# Services.net
KiCad netlist of a schematic drawn in Altium Designer
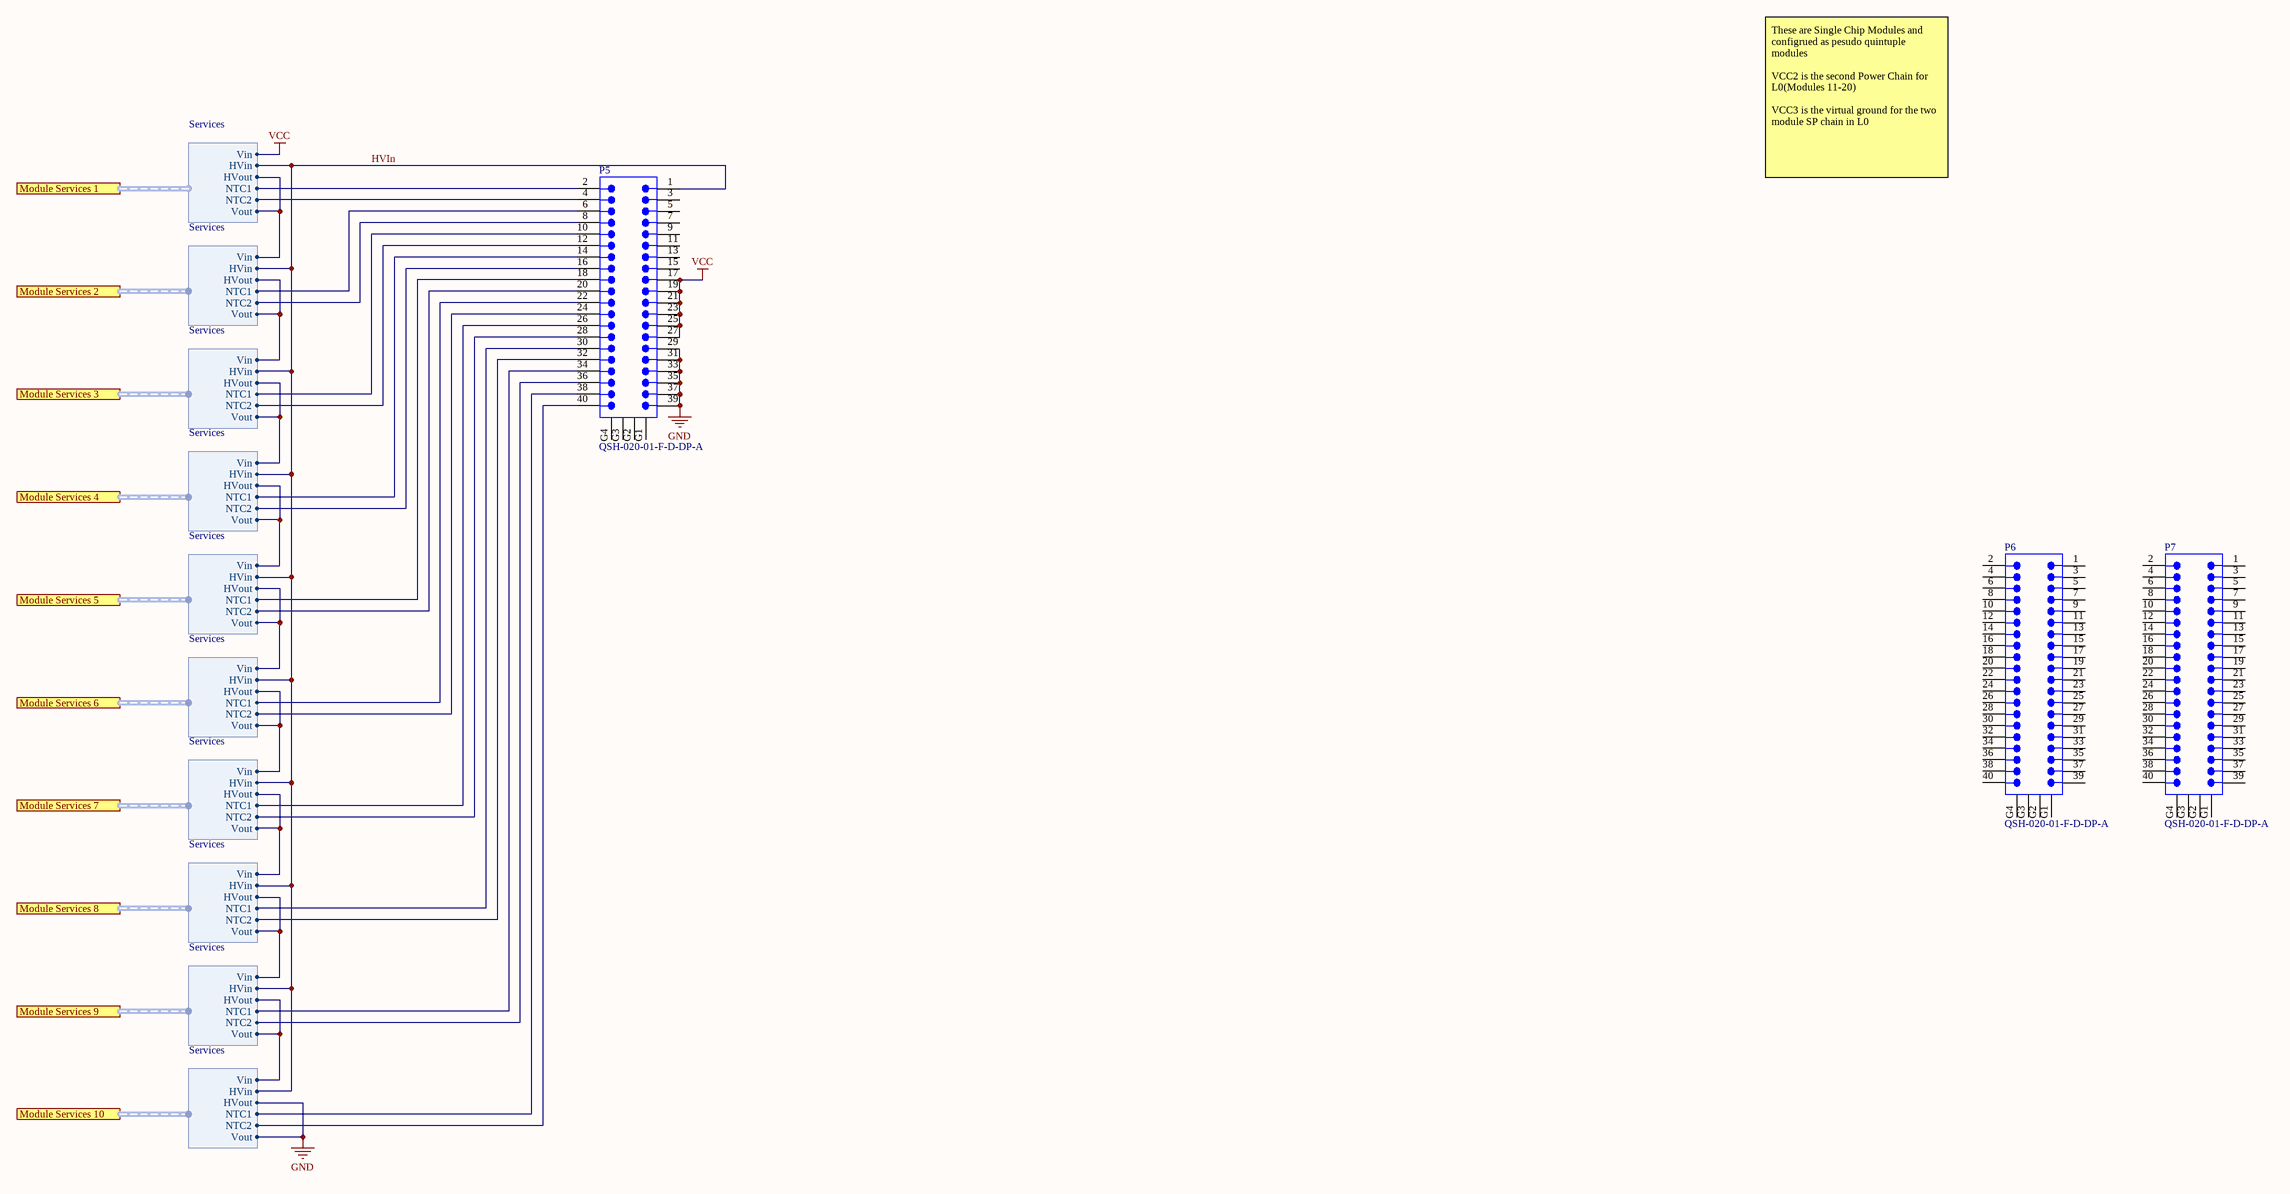
[diagram p0: Services.SchDoc]

(export (version "E")
  (design (tool "Eeschema 10.0.6"))
  (components
    (comp (ref "P5")
      (value "QSH-020-01-F-D-DP-A")
      (footprint "QSH-020-01-X-D-DP-A")
      (description "Board-to-Board Connector, Differnetial Pair, Vertical, 2-Row, Pitch 0.50mm, 40-Position, Male")
      (libsource (lib "Ring Flex SCH Lib") (part "CN-2P-M-40"))
    )
    (comp (ref "P6")
      (value "QSH-020-01-F-D-DP-A")
      (footprint "QSH-020-01-X-D-DP-A")
      (description "Board-to-Board Connector, Differnetial Pair, Vertical, 2-Row, Pitch 0.50mm, 40-Position, Male")
      (libsource (lib "Ring Flex SCH Lib") (part "CN-2P-M-40"))
    )
    (comp (ref "P7")
      (value "QSH-020-01-F-D-DP-A")
      (footprint "QSH-020-01-X-D-DP-A")
      (description "Board-to-Board Connector, Differnetial Pair, Vertical, 2-Row, Pitch 0.50mm, 40-Position, Male")
      (libsource (lib "Ring Flex SCH Lib") (part "CN-2P-M-40"))
    )
  )
  (nets
    (net (code "2") (name "/HVIn") (class "Default")
      (node (ref "P5") (pin "1") (pinfunction "1_1") (pintype "passive"))
    )
    (net (code "4") (name "GND") (class "Default")
      (node (ref "P5") (pin "29") (pinfunction "24_29") (pintype "passive"))
      (node (ref "P5") (pin "31") (pinfunction "25_31") (pintype "passive"))
      (node (ref "P5") (pin "33") (pinfunction "26_33") (pintype "passive"))
      (node (ref "P5") (pin "35") (pinfunction "27_35") (pintype "passive"))
      (node (ref "P5") (pin "37") (pinfunction "28_37") (pintype "passive"))
      (node (ref "P5") (pin "39") (pinfunction "29_39") (pintype "passive"))
    )
    (net (code "5") (name "VCC") (class "Default")
      (node (ref "P5") (pin "17") (pinfunction "17_17") (pintype "passive"))
      (node (ref "P5") (pin "19") (pinfunction "19_19") (pintype "passive"))
      (node (ref "P5") (pin "21") (pinfunction "20_21") (pintype "passive"))
      (node (ref "P5") (pin "23") (pinfunction "21_23") (pintype "passive"))
      (node (ref "P5") (pin "25") (pinfunction "22_25") (pintype "passive"))
      (node (ref "P5") (pin "27") (pinfunction "23_27") (pintype "passive"))
    )
    (net (code "6") (name "unconnected-(P5-21-Pad22)") (class "Default")
      (node (ref "P5") (pin "22") (pinfunction "21_22") (pintype "passive"))
    )
    (net (code "7") (name "unconnected-(P5-22-Pad24)") (class "Default")
      (node (ref "P5") (pin "24") (pinfunction "22_24") (pintype "passive"))
    )
    (net (code "8") (name "unconnected-(P5-23-Pad26)") (class "Default")
      (node (ref "P5") (pin "26") (pinfunction "23_26") (pintype "passive"))
    )
    (net (code "9") (name "unconnected-(P5-24-Pad28)") (class "Default")
      (node (ref "P5") (pin "28") (pinfunction "24_28") (pintype "passive"))
    )
    (net (code "10") (name "unconnected-(P5-25-Pad30)") (class "Default")
      (node (ref "P5") (pin "30") (pinfunction "25_30") (pintype "passive"))
    )
    (net (code "11") (name "unconnected-(P5-26-Pad32)") (class "Default")
      (node (ref "P5") (pin "32") (pinfunction "26_32") (pintype "passive"))
    )
    (net (code "12") (name "unconnected-(P5-27-Pad34)") (class "Default")
      (node (ref "P5") (pin "34") (pinfunction "27_34") (pintype "passive"))
    )
    (net (code "13") (name "unconnected-(P5-28-Pad36)") (class "Default")
      (node (ref "P5") (pin "36") (pinfunction "28_36") (pintype "passive"))
    )
    (net (code "14") (name "unconnected-(P5-29-Pad38)") (class "Default")
      (node (ref "P5") (pin "38") (pinfunction "29_38") (pintype "passive"))
    )
    (net (code "15") (name "unconnected-(P5-30-Pad40)") (class "Default")
      (node (ref "P5") (pin "40") (pinfunction "30_40") (pintype "passive"))
    )
    (net (code "16") (name "unconnected-(P5-Pad2)") (class "Default")
      (node (ref "P5") (pin "2") (pinfunction "2_2") (pintype "passive"))
    )
    (net (code "17") (name "unconnected-(P5-Pad3)") (class "Default")
      (node (ref "P5") (pin "3") (pinfunction "3_3") (pintype "passive"))
    )
    (net (code "18") (name "unconnected-(P5-Pad4)") (class "Default")
      (node (ref "P5") (pin "4") (pinfunction "4_4") (pintype "passive"))
    )
    (net (code "19") (name "unconnected-(P5-Pad5)") (class "Default")
      (node (ref "P5") (pin "5") (pinfunction "5_5") (pintype "passive"))
    )
    (net (code "20") (name "unconnected-(P5-Pad6)") (class "Default")
      (node (ref "P5") (pin "6") (pinfunction "6_6") (pintype "passive"))
    )
    (net (code "21") (name "unconnected-(P5-Pad7)") (class "Default")
      (node (ref "P5") (pin "7") (pinfunction "7_7") (pintype "passive"))
    )
    (net (code "22") (name "unconnected-(P5-Pad8)") (class "Default")
      (node (ref "P5") (pin "8") (pinfunction "8_8") (pintype "passive"))
    )
    (net (code "23") (name "unconnected-(P5-Pad9)") (class "Default")
      (node (ref "P5") (pin "9") (pinfunction "9_9") (pintype "passive"))
    )
    (net (code "24") (name "unconnected-(P5-Pad10)") (class "Default")
      (node (ref "P5") (pin "10") (pinfunction "10_10") (pintype "passive"))
    )
    (net (code "25") (name "unconnected-(P5-Pad11)") (class "Default")
      (node (ref "P5") (pin "11") (pinfunction "11_11") (pintype "passive"))
    )
    (net (code "26") (name "unconnected-(P5-Pad12)") (class "Default")
      (node (ref "P5") (pin "12") (pinfunction "12_12") (pintype "passive"))
    )
    (net (code "27") (name "unconnected-(P5-Pad13)") (class "Default")
      (node (ref "P5") (pin "13") (pinfunction "13_13") (pintype "passive"))
    )
    (net (code "28") (name "unconnected-(P5-Pad14)") (class "Default")
      (node (ref "P5") (pin "14") (pinfunction "14_14") (pintype "passive"))
    )
    (net (code "29") (name "unconnected-(P5-Pad15)") (class "Default")
      (node (ref "P5") (pin "15") (pinfunction "15_15") (pintype "passive"))
    )
    (net (code "30") (name "unconnected-(P5-Pad16)") (class "Default")
      (node (ref "P5") (pin "16") (pinfunction "16_16") (pintype "passive"))
    )
    (net (code "31") (name "unconnected-(P5-Pad18)") (class "Default")
      (node (ref "P5") (pin "18") (pinfunction "18_18") (pintype "passive"))
    )
    (net (code "32") (name "unconnected-(P5-Pad20)") (class "Default")
      (node (ref "P5") (pin "20") (pinfunction "20_20") (pintype "passive"))
    )
    (net (code "33") (name "unconnected-(P5-PadG1)") (class "Default")
      (node (ref "P5") (pin "G1") (pinfunction "G1_G1") (pintype "passive"))
    )
    (net (code "34") (name "unconnected-(P5-PadG2)") (class "Default")
      (node (ref "P5") (pin "G2") (pinfunction "G2_G2") (pintype "passive"))
    )
    (net (code "35") (name "unconnected-(P5-PadG3)") (class "Default")
      (node (ref "P5") (pin "G3") (pinfunction "G3_G3") (pintype "passive"))
    )
    (net (code "36") (name "unconnected-(P5-PadG4)") (class "Default")
      (node (ref "P5") (pin "G4") (pinfunction "G4_G4") (pintype "passive"))
    )
    (net (code "37") (name "unconnected-(P6-20-Pad21)") (class "Default")
      (node (ref "P6") (pin "21") (pinfunction "20_21") (pintype "passive"))
    )
    (net (code "38") (name "unconnected-(P6-21-Pad22)") (class "Default")
      (node (ref "P6") (pin "22") (pinfunction "21_22") (pintype "passive"))
    )
    (net (code "39") (name "unconnected-(P6-21-Pad23)") (class "Default")
      (node (ref "P6") (pin "23") (pinfunction "21_23") (pintype "passive"))
    )
    (net (code "40") (name "unconnected-(P6-22-Pad24)") (class "Default")
      (node (ref "P6") (pin "24") (pinfunction "22_24") (pintype "passive"))
    )
    (net (code "41") (name "unconnected-(P6-22-Pad25)") (class "Default")
      (node (ref "P6") (pin "25") (pinfunction "22_25") (pintype "passive"))
    )
    (net (code "42") (name "unconnected-(P6-23-Pad26)") (class "Default")
      (node (ref "P6") (pin "26") (pinfunction "23_26") (pintype "passive"))
    )
    (net (code "43") (name "unconnected-(P6-23-Pad27)") (class "Default")
      (node (ref "P6") (pin "27") (pinfunction "23_27") (pintype "passive"))
    )
    (net (code "44") (name "unconnected-(P6-24-Pad28)") (class "Default")
      (node (ref "P6") (pin "28") (pinfunction "24_28") (pintype "passive"))
    )
    (net (code "45") (name "unconnected-(P6-24-Pad29)") (class "Default")
      (node (ref "P6") (pin "29") (pinfunction "24_29") (pintype "passive"))
    )
    (net (code "46") (name "unconnected-(P6-25-Pad30)") (class "Default")
      (node (ref "P6") (pin "30") (pinfunction "25_30") (pintype "passive"))
    )
    (net (code "47") (name "unconnected-(P6-25-Pad31)") (class "Default")
      (node (ref "P6") (pin "31") (pinfunction "25_31") (pintype "passive"))
    )
    (net (code "48") (name "unconnected-(P6-26-Pad32)") (class "Default")
      (node (ref "P6") (pin "32") (pinfunction "26_32") (pintype "passive"))
    )
    (net (code "49") (name "unconnected-(P6-26-Pad33)") (class "Default")
      (node (ref "P6") (pin "33") (pinfunction "26_33") (pintype "passive"))
    )
    (net (code "50") (name "unconnected-(P6-27-Pad34)") (class "Default")
      (node (ref "P6") (pin "34") (pinfunction "27_34") (pintype "passive"))
    )
    (net (code "51") (name "unconnected-(P6-27-Pad35)") (class "Default")
      (node (ref "P6") (pin "35") (pinfunction "27_35") (pintype "passive"))
    )
    (net (code "52") (name "unconnected-(P6-28-Pad36)") (class "Default")
      (node (ref "P6") (pin "36") (pinfunction "28_36") (pintype "passive"))
    )
    (net (code "53") (name "unconnected-(P6-28-Pad37)") (class "Default")
      (node (ref "P6") (pin "37") (pinfunction "28_37") (pintype "passive"))
    )
    (net (code "54") (name "unconnected-(P6-29-Pad38)") (class "Default")
      (node (ref "P6") (pin "38") (pinfunction "29_38") (pintype "passive"))
    )
    (net (code "55") (name "unconnected-(P6-29-Pad39)") (class "Default")
      (node (ref "P6") (pin "39") (pinfunction "29_39") (pintype "passive"))
    )
    (net (code "56") (name "unconnected-(P6-30-Pad40)") (class "Default")
      (node (ref "P6") (pin "40") (pinfunction "30_40") (pintype "passive"))
    )
    (net (code "57") (name "unconnected-(P6-Pad1)") (class "Default")
      (node (ref "P6") (pin "1") (pinfunction "1_1") (pintype "passive"))
    )
    (net (code "58") (name "unconnected-(P6-Pad2)") (class "Default")
      (node (ref "P6") (pin "2") (pinfunction "2_2") (pintype "passive"))
    )
    (net (code "59") (name "unconnected-(P6-Pad3)") (class "Default")
      (node (ref "P6") (pin "3") (pinfunction "3_3") (pintype "passive"))
    )
    (net (code "60") (name "unconnected-(P6-Pad4)") (class "Default")
      (node (ref "P6") (pin "4") (pinfunction "4_4") (pintype "passive"))
    )
    (net (code "61") (name "unconnected-(P6-Pad5)") (class "Default")
      (node (ref "P6") (pin "5") (pinfunction "5_5") (pintype "passive"))
    )
    (net (code "62") (name "unconnected-(P6-Pad6)") (class "Default")
      (node (ref "P6") (pin "6") (pinfunction "6_6") (pintype "passive"))
    )
    (net (code "63") (name "unconnected-(P6-Pad7)") (class "Default")
      (node (ref "P6") (pin "7") (pinfunction "7_7") (pintype "passive"))
    )
    (net (code "64") (name "unconnected-(P6-Pad8)") (class "Default")
      (node (ref "P6") (pin "8") (pinfunction "8_8") (pintype "passive"))
    )
    (net (code "65") (name "unconnected-(P6-Pad9)") (class "Default")
      (node (ref "P6") (pin "9") (pinfunction "9_9") (pintype "passive"))
    )
    (net (code "66") (name "unconnected-(P6-Pad10)") (class "Default")
      (node (ref "P6") (pin "10") (pinfunction "10_10") (pintype "passive"))
    )
    (net (code "67") (name "unconnected-(P6-Pad11)") (class "Default")
      (node (ref "P6") (pin "11") (pinfunction "11_11") (pintype "passive"))
    )
    (net (code "68") (name "unconnected-(P6-Pad12)") (class "Default")
      (node (ref "P6") (pin "12") (pinfunction "12_12") (pintype "passive"))
    )
    (net (code "69") (name "unconnected-(P6-Pad13)") (class "Default")
      (node (ref "P6") (pin "13") (pinfunction "13_13") (pintype "passive"))
    )
    (net (code "70") (name "unconnected-(P6-Pad14)") (class "Default")
      (node (ref "P6") (pin "14") (pinfunction "14_14") (pintype "passive"))
    )
    (net (code "71") (name "unconnected-(P6-Pad15)") (class "Default")
      (node (ref "P6") (pin "15") (pinfunction "15_15") (pintype "passive"))
    )
    (net (code "72") (name "unconnected-(P6-Pad16)") (class "Default")
      (node (ref "P6") (pin "16") (pinfunction "16_16") (pintype "passive"))
    )
    (net (code "73") (name "unconnected-(P6-Pad17)") (class "Default")
      (node (ref "P6") (pin "17") (pinfunction "17_17") (pintype "passive"))
    )
    (net (code "74") (name "unconnected-(P6-Pad18)") (class "Default")
      (node (ref "P6") (pin "18") (pinfunction "18_18") (pintype "passive"))
    )
    (net (code "75") (name "unconnected-(P6-Pad19)") (class "Default")
      (node (ref "P6") (pin "19") (pinfunction "19_19") (pintype "passive"))
    )
    (net (code "76") (name "unconnected-(P6-Pad20)") (class "Default")
      (node (ref "P6") (pin "20") (pinfunction "20_20") (pintype "passive"))
    )
    (net (code "77") (name "unconnected-(P6-PadG1)") (class "Default")
      (node (ref "P6") (pin "G1") (pinfunction "G1_G1") (pintype "passive"))
    )
    (net (code "78") (name "unconnected-(P6-PadG2)") (class "Default")
      (node (ref "P6") (pin "G2") (pinfunction "G2_G2") (pintype "passive"))
    )
    (net (code "79") (name "unconnected-(P6-PadG3)") (class "Default")
      (node (ref "P6") (pin "G3") (pinfunction "G3_G3") (pintype "passive"))
    )
    (net (code "80") (name "unconnected-(P6-PadG4)") (class "Default")
      (node (ref "P6") (pin "G4") (pinfunction "G4_G4") (pintype "passive"))
    )
    (net (code "81") (name "unconnected-(P7-20-Pad21)") (class "Default")
      (node (ref "P7") (pin "21") (pinfunction "20_21") (pintype "passive"))
    )
    (net (code "82") (name "unconnected-(P7-21-Pad22)") (class "Default")
      (node (ref "P7") (pin "22") (pinfunction "21_22") (pintype "passive"))
    )
    (net (code "83") (name "unconnected-(P7-21-Pad23)") (class "Default")
      (node (ref "P7") (pin "23") (pinfunction "21_23") (pintype "passive"))
    )
    (net (code "84") (name "unconnected-(P7-22-Pad24)") (class "Default")
      (node (ref "P7") (pin "24") (pinfunction "22_24") (pintype "passive"))
    )
    (net (code "85") (name "unconnected-(P7-22-Pad25)") (class "Default")
      (node (ref "P7") (pin "25") (pinfunction "22_25") (pintype "passive"))
    )
    (net (code "86") (name "unconnected-(P7-23-Pad26)") (class "Default")
      (node (ref "P7") (pin "26") (pinfunction "23_26") (pintype "passive"))
    )
    (net (code "87") (name "unconnected-(P7-23-Pad27)") (class "Default")
      (node (ref "P7") (pin "27") (pinfunction "23_27") (pintype "passive"))
    )
    (net (code "88") (name "unconnected-(P7-24-Pad28)") (class "Default")
      (node (ref "P7") (pin "28") (pinfunction "24_28") (pintype "passive"))
    )
    (net (code "89") (name "unconnected-(P7-24-Pad29)") (class "Default")
      (node (ref "P7") (pin "29") (pinfunction "24_29") (pintype "passive"))
    )
    (net (code "90") (name "unconnected-(P7-25-Pad30)") (class "Default")
      (node (ref "P7") (pin "30") (pinfunction "25_30") (pintype "passive"))
    )
    (net (code "91") (name "unconnected-(P7-25-Pad31)") (class "Default")
      (node (ref "P7") (pin "31") (pinfunction "25_31") (pintype "passive"))
    )
    (net (code "92") (name "unconnected-(P7-26-Pad32)") (class "Default")
      (node (ref "P7") (pin "32") (pinfunction "26_32") (pintype "passive"))
    )
    (net (code "93") (name "unconnected-(P7-26-Pad33)") (class "Default")
      (node (ref "P7") (pin "33") (pinfunction "26_33") (pintype "passive"))
    )
    (net (code "94") (name "unconnected-(P7-27-Pad34)") (class "Default")
      (node (ref "P7") (pin "34") (pinfunction "27_34") (pintype "passive"))
    )
    (net (code "95") (name "unconnected-(P7-27-Pad35)") (class "Default")
      (node (ref "P7") (pin "35") (pinfunction "27_35") (pintype "passive"))
    )
    (net (code "96") (name "unconnected-(P7-28-Pad36)") (class "Default")
      (node (ref "P7") (pin "36") (pinfunction "28_36") (pintype "passive"))
    )
    (net (code "97") (name "unconnected-(P7-28-Pad37)") (class "Default")
      (node (ref "P7") (pin "37") (pinfunction "28_37") (pintype "passive"))
    )
    (net (code "98") (name "unconnected-(P7-29-Pad38)") (class "Default")
      (node (ref "P7") (pin "38") (pinfunction "29_38") (pintype "passive"))
    )
    (net (code "99") (name "unconnected-(P7-29-Pad39)") (class "Default")
      (node (ref "P7") (pin "39") (pinfunction "29_39") (pintype "passive"))
    )
    (net (code "100") (name "unconnected-(P7-30-Pad40)") (class "Default")
      (node (ref "P7") (pin "40") (pinfunction "30_40") (pintype "passive"))
    )
    (net (code "101") (name "unconnected-(P7-Pad1)") (class "Default")
      (node (ref "P7") (pin "1") (pinfunction "1_1") (pintype "passive"))
    )
    (net (code "102") (name "unconnected-(P7-Pad2)") (class "Default")
      (node (ref "P7") (pin "2") (pinfunction "2_2") (pintype "passive"))
    )
    (net (code "103") (name "unconnected-(P7-Pad3)") (class "Default")
      (node (ref "P7") (pin "3") (pinfunction "3_3") (pintype "passive"))
    )
    (net (code "104") (name "unconnected-(P7-Pad4)") (class "Default")
      (node (ref "P7") (pin "4") (pinfunction "4_4") (pintype "passive"))
    )
    (net (code "105") (name "unconnected-(P7-Pad5)") (class "Default")
      (node (ref "P7") (pin "5") (pinfunction "5_5") (pintype "passive"))
    )
    (net (code "106") (name "unconnected-(P7-Pad6)") (class "Default")
      (node (ref "P7") (pin "6") (pinfunction "6_6") (pintype "passive"))
    )
    (net (code "107") (name "unconnected-(P7-Pad7)") (class "Default")
      (node (ref "P7") (pin "7") (pinfunction "7_7") (pintype "passive"))
    )
    (net (code "108") (name "unconnected-(P7-Pad8)") (class "Default")
      (node (ref "P7") (pin "8") (pinfunction "8_8") (pintype "passive"))
    )
    (net (code "109") (name "unconnected-(P7-Pad9)") (class "Default")
      (node (ref "P7") (pin "9") (pinfunction "9_9") (pintype "passive"))
    )
    (net (code "110") (name "unconnected-(P7-Pad10)") (class "Default")
      (node (ref "P7") (pin "10") (pinfunction "10_10") (pintype "passive"))
    )
    (net (code "111") (name "unconnected-(P7-Pad11)") (class "Default")
      (node (ref "P7") (pin "11") (pinfunction "11_11") (pintype "passive"))
    )
    (net (code "112") (name "unconnected-(P7-Pad12)") (class "Default")
      (node (ref "P7") (pin "12") (pinfunction "12_12") (pintype "passive"))
    )
    (net (code "113") (name "unconnected-(P7-Pad13)") (class "Default")
      (node (ref "P7") (pin "13") (pinfunction "13_13") (pintype "passive"))
    )
    (net (code "114") (name "unconnected-(P7-Pad14)") (class "Default")
      (node (ref "P7") (pin "14") (pinfunction "14_14") (pintype "passive"))
    )
    (net (code "115") (name "unconnected-(P7-Pad15)") (class "Default")
      (node (ref "P7") (pin "15") (pinfunction "15_15") (pintype "passive"))
    )
    (net (code "116") (name "unconnected-(P7-Pad16)") (class "Default")
      (node (ref "P7") (pin "16") (pinfunction "16_16") (pintype "passive"))
    )
    (net (code "117") (name "unconnected-(P7-Pad17)") (class "Default")
      (node (ref "P7") (pin "17") (pinfunction "17_17") (pintype "passive"))
    )
    (net (code "118") (name "unconnected-(P7-Pad18)") (class "Default")
      (node (ref "P7") (pin "18") (pinfunction "18_18") (pintype "passive"))
    )
    (net (code "119") (name "unconnected-(P7-Pad19)") (class "Default")
      (node (ref "P7") (pin "19") (pinfunction "19_19") (pintype "passive"))
    )
    (net (code "120") (name "unconnected-(P7-Pad20)") (class "Default")
      (node (ref "P7") (pin "20") (pinfunction "20_20") (pintype "passive"))
    )
    (net (code "121") (name "unconnected-(P7-PadG1)") (class "Default")
      (node (ref "P7") (pin "G1") (pinfunction "G1_G1") (pintype "passive"))
    )
    (net (code "122") (name "unconnected-(P7-PadG2)") (class "Default")
      (node (ref "P7") (pin "G2") (pinfunction "G2_G2") (pintype "passive"))
    )
    (net (code "123") (name "unconnected-(P7-PadG3)") (class "Default")
      (node (ref "P7") (pin "G3") (pinfunction "G3_G3") (pintype "passive"))
    )
    (net (code "124") (name "unconnected-(P7-PadG4)") (class "Default")
      (node (ref "P7") (pin "G4") (pinfunction "G4_G4") (pintype "passive"))
    )
  )
)
